# P_V_S_AVINASH_AS-1.net
KiCad netlist of a schematic drawn in EAGLE
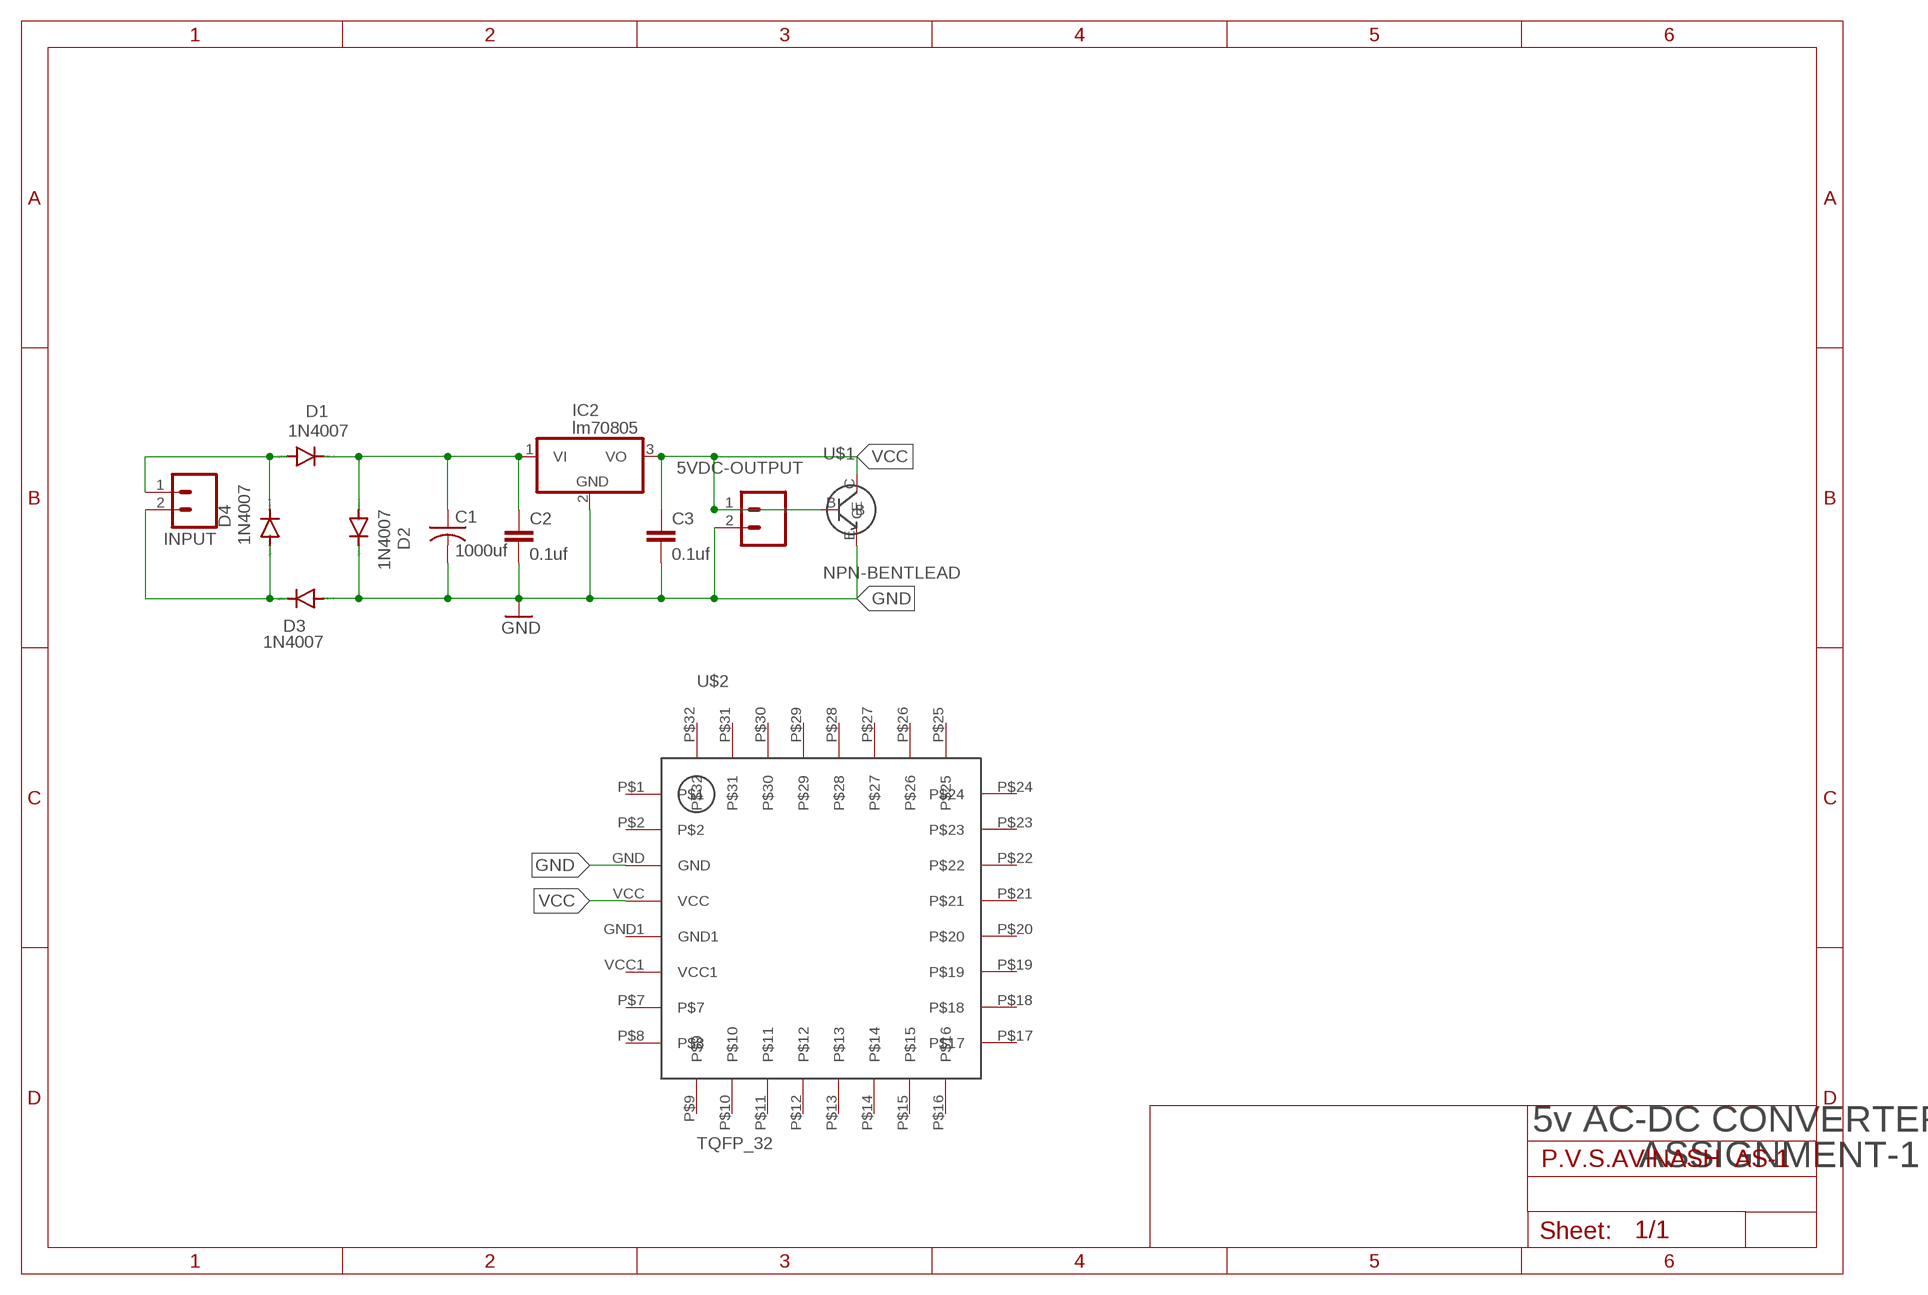
[diagram p0: schematic, sheet 1]

(export (version "E")
  (design (tool "Eeschema 10.0.6"))
  (components
    (comp (ref "5VDC-OUTPUT")
      (value "M02")
      (footprint "eagle-import:02P")
      (libsource (lib "eagle-import") (part "M02"))
    )
    (comp (ref "C1")
      (value "1000uf")
      (footprint "eagle-import:C025-024X044")
      (libsource (lib "eagle-import") (part "C-US025-024X044"))
    )
    (comp (ref "C2")
      (value "0.1uf")
      (footprint "eagle-import:C025-025X050")
      (libsource (lib "eagle-import") (part "C-EU025-025X050"))
    )
    (comp (ref "C3")
      (value "0.1uf")
      (footprint "eagle-import:C025-025X050")
      (libsource (lib "eagle-import") (part "C-EU025-025X050"))
    )
    (comp (ref "D1")
      (value "1N4007")
      (footprint "eagle-import:DO41-10")
      (libsource (lib "eagle-import") (part "1N4004"))
    )
    (comp (ref "D2")
      (value "1N4007")
      (footprint "eagle-import:DO41-10")
      (libsource (lib "eagle-import") (part "1N4004"))
    )
    (comp (ref "D3")
      (value "1N4007")
      (footprint "eagle-import:DO41-10")
      (libsource (lib "eagle-import") (part "1N4004"))
    )
    (comp (ref "D4")
      (value "1N4007")
      (footprint "eagle-import:DO41-10")
      (libsource (lib "eagle-import") (part "1N4004"))
    )
    (comp (ref "IC2")
      (value "lm70805")
      (footprint "eagle-import:TO220V")
      (libsource (lib "eagle-import") (part "78TV6"))
    )
    (comp (ref "INPUT")
      (value "M02")
      (footprint "eagle-import:02P")
      (libsource (lib "eagle-import") (part "M02"))
    )
    (comp (ref "U$1")
      (value "NPN-BENTLEAD")
      (footprint "eagle-import:BENT-LEAD")
      (libsource (lib "eagle-import") (part "NPN-BENTLEAD"))
    )
    (comp (ref "U$2")
      (value "TQFP_32")
      (footprint "eagle-import:TQFP_32")
      (libsource (lib "eagle-import") (part "TQFP_32"))
    )
  )
  (nets
    (net (code "1") (name "GND") (class "Default")
      (node (ref "5VDC-OUTPUT") (pin "2") (pinfunction "2_2") (pintype "passive"))
      (node (ref "C1") (pin "2") (pinfunction "2_2") (pintype "passive"))
      (node (ref "C2") (pin "2") (pinfunction "2_2") (pintype "passive"))
      (node (ref "C3") (pin "2") (pinfunction "2_2") (pintype "passive"))
      (node (ref "D2") (pin "C") (pinfunction "C_C") (pintype "passive"))
      (node (ref "D3") (pin "A") (pinfunction "A_A") (pintype "passive"))
      (node (ref "IC2") (pin "2") (pinfunction "GND_2") (pintype "passive"))
      (node (ref "U$1") (pin "E") (pinfunction "E_E") (pintype "bidirectional"))
      (node (ref "U$2") (pin "GND") (pinfunction "GND_GND") (pintype "bidirectional"))
    )
    (net (code "2") (name "Net-(D1-PadA)") (class "Default")
      (node (ref "D1") (pin "A") (pinfunction "A_A") (pintype "passive"))
      (node (ref "D4") (pin "C") (pinfunction "C_C") (pintype "passive"))
      (node (ref "INPUT") (pin "1") (pinfunction "1_1") (pintype "passive"))
    )
    (net (code "3") (name "Net-(D3-PadC)") (class "Default")
      (node (ref "D3") (pin "C") (pinfunction "C_C") (pintype "passive"))
      (node (ref "D4") (pin "A") (pinfunction "A_A") (pintype "passive"))
      (node (ref "INPUT") (pin "2") (pinfunction "2_2") (pintype "passive"))
    )
    (net (code "4") (name "Net-(IC2-VI)") (class "Default")
      (node (ref "C1") (pin "1") (pinfunction "1_1") (pintype "passive"))
      (node (ref "C2") (pin "1") (pinfunction "1_1") (pintype "passive"))
      (node (ref "D1") (pin "C") (pinfunction "C_C") (pintype "passive"))
      (node (ref "D2") (pin "A") (pinfunction "A_A") (pintype "passive"))
      (node (ref "IC2") (pin "1") (pinfunction "VI_1") (pintype "input"))
    )
    (net (code "5") (name "VCC") (class "Default")
      (node (ref "5VDC-OUTPUT") (pin "1") (pinfunction "1_1") (pintype "passive"))
      (node (ref "C3") (pin "1") (pinfunction "1_1") (pintype "passive"))
      (node (ref "IC2") (pin "3") (pinfunction "VO_3") (pintype "passive"))
      (node (ref "U$1") (pin "B") (pinfunction "B_B") (pintype "bidirectional"))
      (node (ref "U$1") (pin "C") (pinfunction "C_C") (pintype "bidirectional"))
      (node (ref "U$2") (pin "VCC") (pinfunction "VCC_VCC") (pintype "bidirectional"))
    )
    (net (code "6") (name "unconnected-(U$2-PadGND1)") (class "Default")
      (node (ref "U$2") (pin "GND1") (pinfunction "GND1_GND1") (pintype "bidirectional"))
    )
    (net (code "7") (name "unconnected-(U$2-PadP$1)") (class "Default")
      (node (ref "U$2") (pin "P$1") (pinfunction "P$1_P$1") (pintype "bidirectional"))
    )
    (net (code "8") (name "unconnected-(U$2-PadP$2)") (class "Default")
      (node (ref "U$2") (pin "P$2") (pinfunction "P$2_P$2") (pintype "bidirectional"))
    )
    (net (code "9") (name "unconnected-(U$2-PadP$7)") (class "Default")
      (node (ref "U$2") (pin "P$7") (pinfunction "P$7_P$7") (pintype "bidirectional"))
    )
    (net (code "10") (name "unconnected-(U$2-PadP$8)") (class "Default")
      (node (ref "U$2") (pin "P$8") (pinfunction "P$8_P$8") (pintype "bidirectional"))
    )
    (net (code "11") (name "unconnected-(U$2-PadP$9)") (class "Default")
      (node (ref "U$2") (pin "P$9") (pinfunction "P$9_P$9") (pintype "bidirectional"))
    )
    (net (code "12") (name "unconnected-(U$2-PadP$10)") (class "Default")
      (node (ref "U$2") (pin "P$10") (pinfunction "P$10_P$10") (pintype "bidirectional"))
    )
    (net (code "13") (name "unconnected-(U$2-PadP$11)") (class "Default")
      (node (ref "U$2") (pin "P$11") (pinfunction "P$11_P$11") (pintype "bidirectional"))
    )
    (net (code "14") (name "unconnected-(U$2-PadP$12)") (class "Default")
      (node (ref "U$2") (pin "P$12") (pinfunction "P$12_P$12") (pintype "bidirectional"))
    )
    (net (code "15") (name "unconnected-(U$2-PadP$13)") (class "Default")
      (node (ref "U$2") (pin "P$13") (pinfunction "P$13_P$13") (pintype "bidirectional"))
    )
    (net (code "16") (name "unconnected-(U$2-PadP$14)") (class "Default")
      (node (ref "U$2") (pin "P$14") (pinfunction "P$14_P$14") (pintype "bidirectional"))
    )
    (net (code "17") (name "unconnected-(U$2-PadP$15)") (class "Default")
      (node (ref "U$2") (pin "P$15") (pinfunction "P$15_P$15") (pintype "bidirectional"))
    )
    (net (code "18") (name "unconnected-(U$2-PadP$16)") (class "Default")
      (node (ref "U$2") (pin "P$16") (pinfunction "P$16_P$16") (pintype "bidirectional"))
    )
    (net (code "19") (name "unconnected-(U$2-PadP$17)") (class "Default")
      (node (ref "U$2") (pin "P$17") (pinfunction "P$17_P$17") (pintype "bidirectional"))
    )
    (net (code "20") (name "unconnected-(U$2-PadP$18)") (class "Default")
      (node (ref "U$2") (pin "P$18") (pinfunction "P$18_P$18") (pintype "bidirectional"))
    )
    (net (code "21") (name "unconnected-(U$2-PadP$19)") (class "Default")
      (node (ref "U$2") (pin "P$19") (pinfunction "P$19_P$19") (pintype "bidirectional"))
    )
    (net (code "22") (name "unconnected-(U$2-PadP$20)") (class "Default")
      (node (ref "U$2") (pin "P$20") (pinfunction "P$20_P$20") (pintype "bidirectional"))
    )
    (net (code "23") (name "unconnected-(U$2-PadP$21)") (class "Default")
      (node (ref "U$2") (pin "P$21") (pinfunction "P$21_P$21") (pintype "bidirectional"))
    )
    (net (code "24") (name "unconnected-(U$2-PadP$22)") (class "Default")
      (node (ref "U$2") (pin "P$22") (pinfunction "P$22_P$22") (pintype "bidirectional"))
    )
    (net (code "25") (name "unconnected-(U$2-PadP$23)") (class "Default")
      (node (ref "U$2") (pin "P$23") (pinfunction "P$23_P$23") (pintype "bidirectional"))
    )
    (net (code "26") (name "unconnected-(U$2-PadP$24)") (class "Default")
      (node (ref "U$2") (pin "P$24") (pinfunction "P$24_P$24") (pintype "bidirectional"))
    )
    (net (code "27") (name "unconnected-(U$2-PadP$25)") (class "Default")
      (node (ref "U$2") (pin "P$25") (pinfunction "P$25_P$25") (pintype "bidirectional"))
    )
    (net (code "28") (name "unconnected-(U$2-PadP$26)") (class "Default")
      (node (ref "U$2") (pin "P$26") (pinfunction "P$26_P$26") (pintype "bidirectional"))
    )
    (net (code "29") (name "unconnected-(U$2-PadP$27)") (class "Default")
      (node (ref "U$2") (pin "P$27") (pinfunction "P$27_P$27") (pintype "bidirectional"))
    )
    (net (code "30") (name "unconnected-(U$2-PadP$28)") (class "Default")
      (node (ref "U$2") (pin "P$28") (pinfunction "P$28_P$28") (pintype "bidirectional"))
    )
    (net (code "31") (name "unconnected-(U$2-PadP$29)") (class "Default")
      (node (ref "U$2") (pin "P$29") (pinfunction "P$29_P$29") (pintype "bidirectional"))
    )
    (net (code "32") (name "unconnected-(U$2-PadP$30)") (class "Default")
      (node (ref "U$2") (pin "P$30") (pinfunction "P$30_P$30") (pintype "bidirectional"))
    )
    (net (code "33") (name "unconnected-(U$2-PadP$31)") (class "Default")
      (node (ref "U$2") (pin "P$31") (pinfunction "P$31_P$31") (pintype "bidirectional"))
    )
    (net (code "34") (name "unconnected-(U$2-PadP$32)") (class "Default")
      (node (ref "U$2") (pin "P$32") (pinfunction "P$32_P$32") (pintype "bidirectional"))
    )
    (net (code "35") (name "unconnected-(U$2-PadVCC1)") (class "Default")
      (node (ref "U$2") (pin "VCC1") (pinfunction "VCC1_VCC1") (pintype "bidirectional"))
    )
  )
)
